# usb_blaster.net
KiCad netlist of a schematic drawn in EAGLE
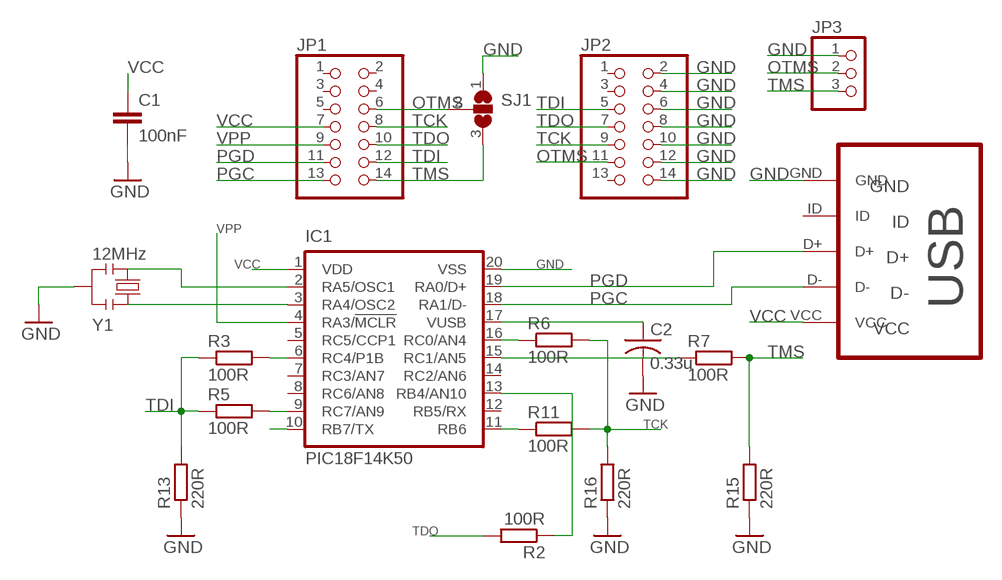
[diagram p0: schematic, sheet 1]

(export (version "E")
  (design (tool "Eeschema 10.0.6"))
  (components
    (comp (ref "C1")
      (value "100nF")
      (footprint "eagle-import:C0805")
      (libsource (lib "eagle-import") (part "C-EUC0805"))
    )
    (comp (ref "C2")
      (value "0.33u")
      (footprint "eagle-import:C0805")
      (libsource (lib "eagle-import") (part "C-USC0805"))
    )
    (comp (ref "IC1")
      (value "PIC18F14K50")
      (footprint "eagle-import:SS20")
      (libsource (lib "eagle-import") (part "PIC18F14K50"))
    )
    (comp (ref "JP1")
      (value "PINHD-2X7")
      (footprint "eagle-import:2X07")
      (libsource (lib "eagle-import") (part "PINHD-2X7"))
    )
    (comp (ref "JP2")
      (value "PINHD-2X7")
      (footprint "eagle-import:2X07")
      (libsource (lib "eagle-import") (part "PINHD-2X7"))
    )
    (comp (ref "JP3")
      (value "PINHD-1X3")
      (footprint "eagle-import:1X03")
      (libsource (lib "eagle-import") (part "PINHD-1X3"))
    )
    (comp (ref "R2")
      (value "100R")
      (footprint "eagle-import:R0805")
      (libsource (lib "eagle-import") (part "R-EU_R0805"))
    )
    (comp (ref "R3")
      (value "100R")
      (footprint "eagle-import:R0805")
      (libsource (lib "eagle-import") (part "R-EU_R0805"))
    )
    (comp (ref "R5")
      (value "100R")
      (footprint "eagle-import:R0805")
      (libsource (lib "eagle-import") (part "R-EU_R0805"))
    )
    (comp (ref "R6")
      (value "100R")
      (footprint "eagle-import:R0805")
      (libsource (lib "eagle-import") (part "R-EU_R0805"))
    )
    (comp (ref "R7")
      (value "100R")
      (footprint "eagle-import:R0805")
      (libsource (lib "eagle-import") (part "R-EU_R0805"))
    )
    (comp (ref "R11")
      (value "100R")
      (footprint "eagle-import:R0805")
      (libsource (lib "eagle-import") (part "R-EU_R0805"))
    )
    (comp (ref "R13")
      (value "220R")
      (footprint "eagle-import:R0805")
      (libsource (lib "eagle-import") (part "R-EU_R0805"))
    )
    (comp (ref "R15")
      (value "220R")
      (footprint "eagle-import:R0805")
      (libsource (lib "eagle-import") (part "R-EU_R0805"))
    )
    (comp (ref "R16")
      (value "220R")
      (footprint "eagle-import:R0805")
      (libsource (lib "eagle-import") (part "R-EU_R0805"))
    )
    (comp (ref "SJ1")
      (value "SJ2W")
      (footprint "eagle-import:SJ_2")
      (libsource (lib "eagle-import") (part "SJ2W"))
    )
    (comp (ref "U$2")
      (value "MICRO-USB-B")
      (footprint "eagle-import:MICRO_USB_4_LEGS")
      (libsource (lib "eagle-import") (part "MICRO-USB-B"))
    )
    (comp (ref "Y1")
      (value "12MHz")
      (footprint "eagle-import:RESONATOR")
      (fields (field (name "PART_NUMBER") "CSTCE16M0V53-R0"))
      (libsource (lib "eagle-import") (part "0011_CSTCE16M0V53-R0"))
    )
  )
  (nets
    (net (code "1") (name "/OTMS") (class "Default")
      (node (ref "JP1") (pin "6") (pinfunction "6_6") (pintype "passive"))
      (node (ref "JP2") (pin "11") (pinfunction "11_11") (pintype "passive"))
      (node (ref "JP3") (pin "2") (pinfunction "2_2") (pintype "passive"))
      (node (ref "SJ1") (pin "2") (pinfunction "2_2") (pintype "passive"))
    )
    (net (code "2") (name "/PGC") (class "Default")
      (node (ref "IC1") (pin "18") (pinfunction "RA1/D-_18") (pintype "bidirectional"))
      (node (ref "JP1") (pin "13") (pinfunction "13_13") (pintype "passive"))
      (node (ref "U$2") (pin "D-") (pinfunction "D-_D-") (pintype "bidirectional"))
    )
    (net (code "3") (name "/PGD") (class "Default")
      (node (ref "IC1") (pin "19") (pinfunction "RA0/D+_19") (pintype "bidirectional"))
      (node (ref "JP1") (pin "11") (pinfunction "11_11") (pintype "passive"))
      (node (ref "U$2") (pin "D+") (pinfunction "D+_D+") (pintype "bidirectional"))
    )
    (net (code "4") (name "/TCK") (class "Default")
      (node (ref "JP1") (pin "8") (pinfunction "8_8") (pintype "passive"))
      (node (ref "JP2") (pin "9") (pinfunction "9_9") (pintype "passive"))
      (node (ref "R11") (pin "2") (pinfunction "2_2") (pintype "passive"))
      (node (ref "R16") (pin "2") (pinfunction "2_2") (pintype "passive"))
      (node (ref "R6") (pin "2") (pinfunction "2_2") (pintype "passive"))
    )
    (net (code "5") (name "/TDI") (class "Default")
      (node (ref "JP1") (pin "12") (pinfunction "12_12") (pintype "passive"))
      (node (ref "JP2") (pin "5") (pinfunction "5_5") (pintype "passive"))
      (node (ref "R13") (pin "2") (pinfunction "2_2") (pintype "passive"))
      (node (ref "R3") (pin "1") (pinfunction "1_1") (pintype "passive"))
      (node (ref "R5") (pin "1") (pinfunction "1_1") (pintype "passive"))
    )
    (net (code "6") (name "/TDO") (class "Default")
      (node (ref "JP1") (pin "10") (pinfunction "10_10") (pintype "passive"))
      (node (ref "JP2") (pin "7") (pinfunction "7_7") (pintype "passive"))
      (node (ref "R2") (pin "2") (pinfunction "2_2") (pintype "passive"))
    )
    (net (code "7") (name "/TMS") (class "Default")
      (node (ref "JP1") (pin "14") (pinfunction "14_14") (pintype "passive"))
      (node (ref "JP3") (pin "3") (pinfunction "3_3") (pintype "passive"))
      (node (ref "R15") (pin "2") (pinfunction "2_2") (pintype "passive"))
      (node (ref "R7") (pin "2") (pinfunction "2_2") (pintype "passive"))
      (node (ref "SJ1") (pin "3") (pinfunction "3_3") (pintype "passive"))
    )
    (net (code "8") (name "/VCC") (class "Default")
      (node (ref "C1") (pin "1") (pinfunction "1_1") (pintype "passive"))
      (node (ref "IC1") (pin "1") (pinfunction "VDD_1") (pintype "power_in"))
      (node (ref "JP1") (pin "7") (pinfunction "7_7") (pintype "passive"))
      (node (ref "U$2") (pin "VCC") (pinfunction "VCC_VCC") (pintype "bidirectional"))
    )
    (net (code "9") (name "/VPP") (class "Default")
      (node (ref "IC1") (pin "4") (pinfunction "RA3/~{MCLR}_4") (pintype "bidirectional"))
      (node (ref "JP1") (pin "9") (pinfunction "9_9") (pintype "passive"))
    )
    (net (code "10") (name "GND") (class "Default")
      (node (ref "C1") (pin "2") (pinfunction "2_2") (pintype "passive"))
      (node (ref "C2") (pin "2") (pinfunction "2_2") (pintype "passive"))
      (node (ref "IC1") (pin "20") (pinfunction "VSS_20") (pintype "power_in"))
      (node (ref "JP2") (pin "10") (pinfunction "10_10") (pintype "passive"))
      (node (ref "JP2") (pin "12") (pinfunction "12_12") (pintype "passive"))
      (node (ref "JP2") (pin "14") (pinfunction "14_14") (pintype "passive"))
      (node (ref "JP2") (pin "2") (pinfunction "2_2") (pintype "passive"))
      (node (ref "JP2") (pin "4") (pinfunction "4_4") (pintype "passive"))
      (node (ref "JP2") (pin "6") (pinfunction "6_6") (pintype "passive"))
      (node (ref "JP2") (pin "8") (pinfunction "8_8") (pintype "passive"))
      (node (ref "JP3") (pin "1") (pinfunction "1_1") (pintype "passive"))
      (node (ref "R13") (pin "1") (pinfunction "1_1") (pintype "passive"))
      (node (ref "R15") (pin "1") (pinfunction "1_1") (pintype "passive"))
      (node (ref "R16") (pin "1") (pinfunction "1_1") (pintype "passive"))
      (node (ref "SJ1") (pin "1") (pinfunction "1_1") (pintype "passive"))
      (node (ref "U$2") (pin "GND") (pinfunction "GND_GND") (pintype "bidirectional"))
      (node (ref "Y1") (pin "2") (pinfunction "2_2") (pintype "passive"))
    )
    (net (code "11") (name "Net-(IC1-RA4{slash}OSC2)") (class "Default")
      (node (ref "IC1") (pin "3") (pinfunction "RA4/OSC2_3") (pintype "bidirectional"))
      (node (ref "Y1") (pin "1") (pinfunction "1_1") (pintype "passive"))
    )
    (net (code "12") (name "Net-(IC1-RA5{slash}OSC1)") (class "Default")
      (node (ref "IC1") (pin "2") (pinfunction "RA5/OSC1_2") (pintype "bidirectional"))
      (node (ref "Y1") (pin "3") (pinfunction "3_3") (pintype "passive"))
    )
    (net (code "13") (name "Net-(IC1-RB4{slash}AN10)") (class "Default")
      (node (ref "IC1") (pin "13") (pinfunction "RB4/AN10_13") (pintype "bidirectional"))
      (node (ref "R2") (pin "1") (pinfunction "1_1") (pintype "passive"))
    )
    (net (code "14") (name "Net-(IC1-RB6)") (class "Default")
      (node (ref "IC1") (pin "11") (pinfunction "RB6_11") (pintype "bidirectional"))
      (node (ref "R11") (pin "1") (pinfunction "1_1") (pintype "passive"))
    )
    (net (code "15") (name "Net-(IC1-RC0{slash}AN4)") (class "Default")
      (node (ref "IC1") (pin "16") (pinfunction "RC0/AN4_16") (pintype "bidirectional"))
      (node (ref "R6") (pin "1") (pinfunction "1_1") (pintype "passive"))
    )
    (net (code "16") (name "Net-(IC1-RC1{slash}AN5)") (class "Default")
      (node (ref "IC1") (pin "15") (pinfunction "RC1/AN5_15") (pintype "bidirectional"))
      (node (ref "R7") (pin "1") (pinfunction "1_1") (pintype "passive"))
    )
    (net (code "17") (name "Net-(IC1-RC4{slash}P1B)") (class "Default")
      (node (ref "IC1") (pin "6") (pinfunction "RC4/P1B_6") (pintype "bidirectional"))
      (node (ref "R3") (pin "2") (pinfunction "2_2") (pintype "passive"))
    )
    (net (code "18") (name "Net-(IC1-RC7{slash}AN9)") (class "Default")
      (node (ref "IC1") (pin "9") (pinfunction "RC7/AN9_9") (pintype "bidirectional"))
      (node (ref "R5") (pin "2") (pinfunction "2_2") (pintype "passive"))
    )
    (net (code "19") (name "Net-(IC1-VUSB)") (class "Default")
      (node (ref "C2") (pin "1") (pinfunction "1_1") (pintype "passive"))
      (node (ref "IC1") (pin "17") (pinfunction "VUSB_17") (pintype "bidirectional"))
    )
    (net (code "20") (name "unconnected-(IC1-RB5{slash}RX-Pad12)") (class "Default")
      (node (ref "IC1") (pin "12") (pinfunction "RB5/RX_12") (pintype "bidirectional"))
    )
    (net (code "21") (name "unconnected-(IC1-RB7{slash}TX-Pad10)") (class "Default")
      (node (ref "IC1") (pin "10") (pinfunction "RB7/TX_10") (pintype "bidirectional"))
    )
    (net (code "22") (name "unconnected-(IC1-RC2{slash}AN6-Pad14)") (class "Default")
      (node (ref "IC1") (pin "14") (pinfunction "RC2/AN6_14") (pintype "bidirectional"))
    )
    (net (code "23") (name "unconnected-(IC1-RC3{slash}AN7-Pad7)") (class "Default")
      (node (ref "IC1") (pin "7") (pinfunction "RC3/AN7_7") (pintype "bidirectional"))
    )
    (net (code "24") (name "unconnected-(IC1-RC5{slash}CCP1-Pad5)") (class "Default")
      (node (ref "IC1") (pin "5") (pinfunction "RC5/CCP1_5") (pintype "bidirectional"))
    )
    (net (code "25") (name "unconnected-(IC1-RC6{slash}AN8-Pad8)") (class "Default")
      (node (ref "IC1") (pin "8") (pinfunction "RC6/AN8_8") (pintype "bidirectional"))
    )
    (net (code "26") (name "unconnected-(JP1-Pad1)") (class "Default")
      (node (ref "JP1") (pin "1") (pinfunction "1_1") (pintype "passive"))
    )
    (net (code "27") (name "unconnected-(JP1-Pad2)") (class "Default")
      (node (ref "JP1") (pin "2") (pinfunction "2_2") (pintype "passive"))
    )
    (net (code "28") (name "unconnected-(JP1-Pad3)") (class "Default")
      (node (ref "JP1") (pin "3") (pinfunction "3_3") (pintype "passive"))
    )
    (net (code "29") (name "unconnected-(JP1-Pad4)") (class "Default")
      (node (ref "JP1") (pin "4") (pinfunction "4_4") (pintype "passive"))
    )
    (net (code "30") (name "unconnected-(JP1-Pad5)") (class "Default")
      (node (ref "JP1") (pin "5") (pinfunction "5_5") (pintype "passive"))
    )
    (net (code "31") (name "unconnected-(JP2-Pad1)") (class "Default")
      (node (ref "JP2") (pin "1") (pinfunction "1_1") (pintype "passive"))
    )
    (net (code "32") (name "unconnected-(JP2-Pad3)") (class "Default")
      (node (ref "JP2") (pin "3") (pinfunction "3_3") (pintype "passive"))
    )
    (net (code "33") (name "unconnected-(JP2-Pad13)") (class "Default")
      (node (ref "JP2") (pin "13") (pinfunction "13_13") (pintype "passive"))
    )
    (net (code "34") (name "unconnected-(U$2-PadID)") (class "Default")
      (node (ref "U$2") (pin "ID") (pinfunction "ID_ID") (pintype "bidirectional"))
    )
  )
)
